# working.net
KiCad netlist of a schematic drawn in EAGLE
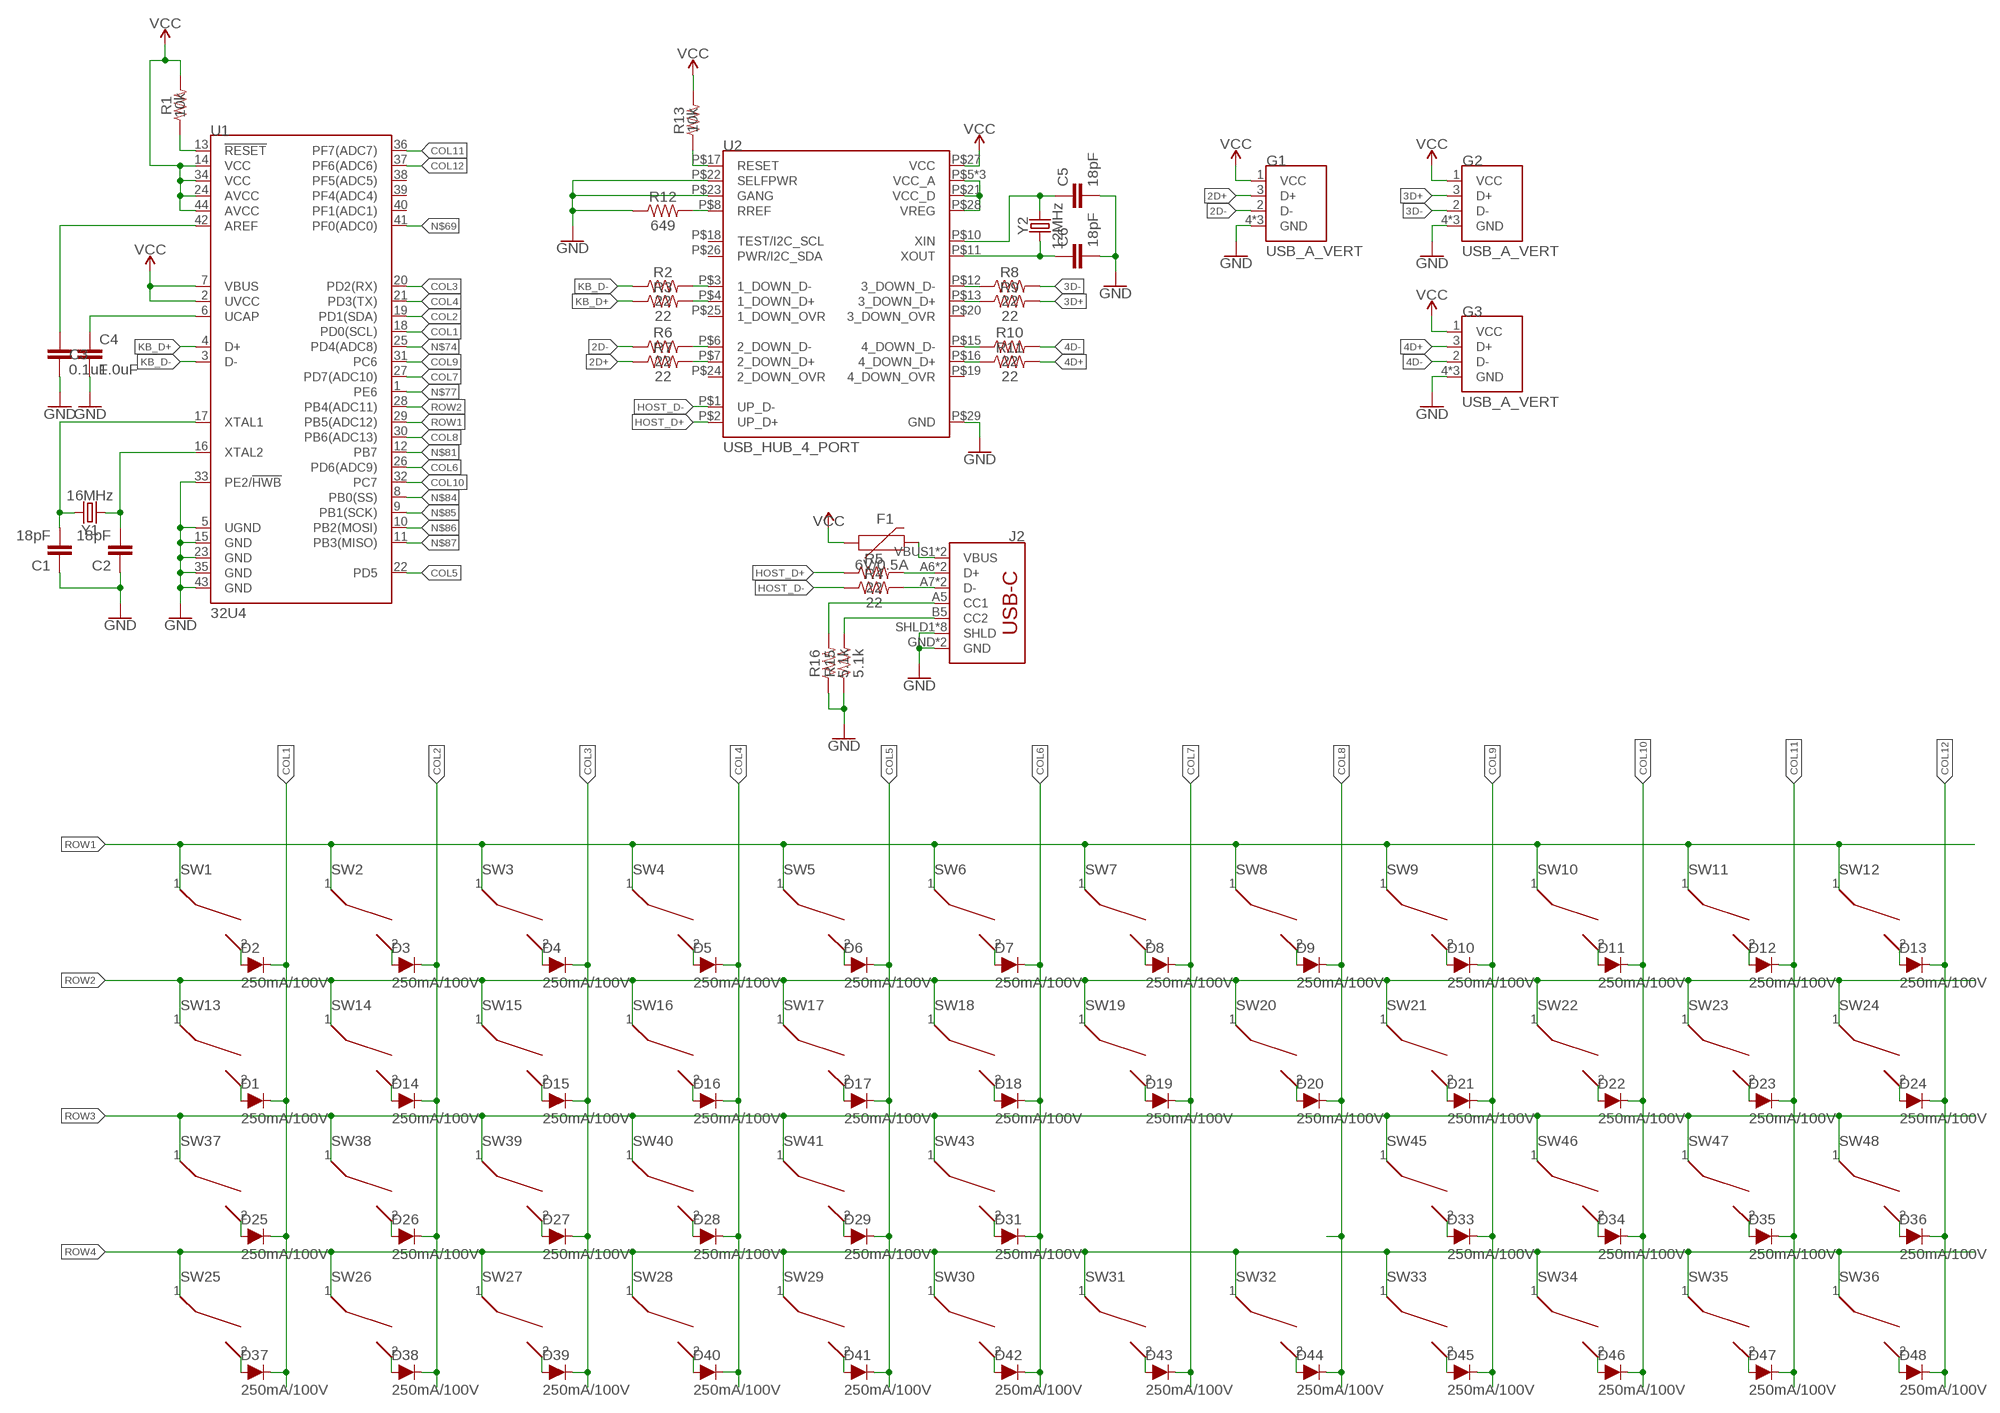
[diagram p0: schematic, sheet 1]

(export (version "E")
  (design (tool "Eeschema 10.0.6"))
  (components
    (comp (ref "C1")
      (value "18pF")
      (footprint "eagle-import:0603")
      (libsource (lib "eagle-import") (part "18PF-0603-50V-5%"))
    )
    (comp (ref "C2")
      (value "18pF")
      (footprint "eagle-import:0603")
      (libsource (lib "eagle-import") (part "18PF-0603-50V-5%"))
    )
    (comp (ref "C3")
      (value "0.1uF")
      (footprint "eagle-import:0603")
      (libsource (lib "eagle-import") (part "0.1UF-0603-25V-(+80/-20%)"))
    )
    (comp (ref "C4")
      (value "1.0uF")
      (footprint "eagle-import:0603")
      (libsource (lib "eagle-import") (part "1.0UF-0603-16V-10%"))
    )
    (comp (ref "C5")
      (value "18pF")
      (footprint "eagle-import:0603")
      (libsource (lib "eagle-import") (part "18PF-0603-50V-5%"))
    )
    (comp (ref "C6")
      (value "18pF")
      (footprint "eagle-import:0603")
      (libsource (lib "eagle-import") (part "18PF-0603-50V-5%"))
    )
    (comp (ref "D1")
      (value "250mA/100V")
      (footprint "eagle-import:SOD-323")
      (libsource (lib "eagle-import") (part "DIODE-BAS16J"))
    )
    (comp (ref "D2")
      (value "250mA/100V")
      (footprint "eagle-import:SOD-323")
      (libsource (lib "eagle-import") (part "DIODE-BAS16J"))
    )
    (comp (ref "D3")
      (value "250mA/100V")
      (footprint "eagle-import:SOD-323")
      (libsource (lib "eagle-import") (part "DIODE-BAS16J"))
    )
    (comp (ref "D4")
      (value "250mA/100V")
      (footprint "eagle-import:SOD-323")
      (libsource (lib "eagle-import") (part "DIODE-BAS16J"))
    )
    (comp (ref "D5")
      (value "250mA/100V")
      (footprint "eagle-import:SOD-323")
      (libsource (lib "eagle-import") (part "DIODE-BAS16J"))
    )
    (comp (ref "D6")
      (value "250mA/100V")
      (footprint "eagle-import:SOD-323")
      (libsource (lib "eagle-import") (part "DIODE-BAS16J"))
    )
    (comp (ref "D7")
      (value "250mA/100V")
      (footprint "eagle-import:SOD-323")
      (libsource (lib "eagle-import") (part "DIODE-BAS16J"))
    )
    (comp (ref "D8")
      (value "250mA/100V")
      (footprint "eagle-import:SOD-323")
      (libsource (lib "eagle-import") (part "DIODE-BAS16J"))
    )
    (comp (ref "D9")
      (value "250mA/100V")
      (footprint "eagle-import:SOD-323")
      (libsource (lib "eagle-import") (part "DIODE-BAS16J"))
    )
    (comp (ref "D10")
      (value "250mA/100V")
      (footprint "eagle-import:SOD-323")
      (libsource (lib "eagle-import") (part "DIODE-BAS16J"))
    )
    (comp (ref "D11")
      (value "250mA/100V")
      (footprint "eagle-import:SOD-323")
      (libsource (lib "eagle-import") (part "DIODE-BAS16J"))
    )
    (comp (ref "D12")
      (value "250mA/100V")
      (footprint "eagle-import:SOD-323")
      (libsource (lib "eagle-import") (part "DIODE-BAS16J"))
    )
    (comp (ref "D13")
      (value "250mA/100V")
      (footprint "eagle-import:SOD-323")
      (libsource (lib "eagle-import") (part "DIODE-BAS16J"))
    )
    (comp (ref "D14")
      (value "250mA/100V")
      (footprint "eagle-import:SOD-323")
      (libsource (lib "eagle-import") (part "DIODE-BAS16J"))
    )
    (comp (ref "D15")
      (value "250mA/100V")
      (footprint "eagle-import:SOD-323")
      (libsource (lib "eagle-import") (part "DIODE-BAS16J"))
    )
    (comp (ref "D16")
      (value "250mA/100V")
      (footprint "eagle-import:SOD-323")
      (libsource (lib "eagle-import") (part "DIODE-BAS16J"))
    )
    (comp (ref "D17")
      (value "250mA/100V")
      (footprint "eagle-import:SOD-323")
      (libsource (lib "eagle-import") (part "DIODE-BAS16J"))
    )
    (comp (ref "D18")
      (value "250mA/100V")
      (footprint "eagle-import:SOD-323")
      (libsource (lib "eagle-import") (part "DIODE-BAS16J"))
    )
    (comp (ref "D19")
      (value "250mA/100V")
      (footprint "eagle-import:SOD-323")
      (libsource (lib "eagle-import") (part "DIODE-BAS16J"))
    )
    (comp (ref "D20")
      (value "250mA/100V")
      (footprint "eagle-import:SOD-323")
      (libsource (lib "eagle-import") (part "DIODE-BAS16J"))
    )
    (comp (ref "D21")
      (value "250mA/100V")
      (footprint "eagle-import:SOD-323")
      (libsource (lib "eagle-import") (part "DIODE-BAS16J"))
    )
    (comp (ref "D22")
      (value "250mA/100V")
      (footprint "eagle-import:SOD-323")
      (libsource (lib "eagle-import") (part "DIODE-BAS16J"))
    )
    (comp (ref "D23")
      (value "250mA/100V")
      (footprint "eagle-import:SOD-323")
      (libsource (lib "eagle-import") (part "DIODE-BAS16J"))
    )
    (comp (ref "D24")
      (value "250mA/100V")
      (footprint "eagle-import:SOD-323")
      (libsource (lib "eagle-import") (part "DIODE-BAS16J"))
    )
    (comp (ref "D25")
      (value "250mA/100V")
      (footprint "eagle-import:SOD-323")
      (libsource (lib "eagle-import") (part "DIODE-BAS16J"))
    )
    (comp (ref "D26")
      (value "250mA/100V")
      (footprint "eagle-import:SOD-323")
      (libsource (lib "eagle-import") (part "DIODE-BAS16J"))
    )
    (comp (ref "D27")
      (value "250mA/100V")
      (footprint "eagle-import:SOD-323")
      (libsource (lib "eagle-import") (part "DIODE-BAS16J"))
    )
    (comp (ref "D28")
      (value "250mA/100V")
      (footprint "eagle-import:SOD-323")
      (libsource (lib "eagle-import") (part "DIODE-BAS16J"))
    )
    (comp (ref "D29")
      (value "250mA/100V")
      (footprint "eagle-import:SOD-323")
      (libsource (lib "eagle-import") (part "DIODE-BAS16J"))
    )
    (comp (ref "D31")
      (value "250mA/100V")
      (footprint "eagle-import:SOD-323")
      (libsource (lib "eagle-import") (part "DIODE-BAS16J"))
    )
    (comp (ref "D33")
      (value "250mA/100V")
      (footprint "eagle-import:SOD-323")
      (libsource (lib "eagle-import") (part "DIODE-BAS16J"))
    )
    (comp (ref "D34")
      (value "250mA/100V")
      (footprint "eagle-import:SOD-323")
      (libsource (lib "eagle-import") (part "DIODE-BAS16J"))
    )
    (comp (ref "D35")
      (value "250mA/100V")
      (footprint "eagle-import:SOD-323")
      (libsource (lib "eagle-import") (part "DIODE-BAS16J"))
    )
    (comp (ref "D36")
      (value "250mA/100V")
      (footprint "eagle-import:SOD-323")
      (libsource (lib "eagle-import") (part "DIODE-BAS16J"))
    )
    (comp (ref "D37")
      (value "250mA/100V")
      (footprint "eagle-import:SOD-323")
      (libsource (lib "eagle-import") (part "DIODE-BAS16J"))
    )
    (comp (ref "D38")
      (value "250mA/100V")
      (footprint "eagle-import:SOD-323")
      (libsource (lib "eagle-import") (part "DIODE-BAS16J"))
    )
    (comp (ref "D39")
      (value "250mA/100V")
      (footprint "eagle-import:SOD-323")
      (libsource (lib "eagle-import") (part "DIODE-BAS16J"))
    )
    (comp (ref "D40")
      (value "250mA/100V")
      (footprint "eagle-import:SOD-323")
      (libsource (lib "eagle-import") (part "DIODE-BAS16J"))
    )
    (comp (ref "D41")
      (value "250mA/100V")
      (footprint "eagle-import:SOD-323")
      (libsource (lib "eagle-import") (part "DIODE-BAS16J"))
    )
    (comp (ref "D42")
      (value "250mA/100V")
      (footprint "eagle-import:SOD-323")
      (libsource (lib "eagle-import") (part "DIODE-BAS16J"))
    )
    (comp (ref "D43")
      (value "250mA/100V")
      (footprint "eagle-import:SOD-323")
      (libsource (lib "eagle-import") (part "DIODE-BAS16J"))
    )
    (comp (ref "D44")
      (value "250mA/100V")
      (footprint "eagle-import:SOD-323")
      (libsource (lib "eagle-import") (part "DIODE-BAS16J"))
    )
    (comp (ref "D45")
      (value "250mA/100V")
      (footprint "eagle-import:SOD-323")
      (libsource (lib "eagle-import") (part "DIODE-BAS16J"))
    )
    (comp (ref "D46")
      (value "250mA/100V")
      (footprint "eagle-import:SOD-323")
      (libsource (lib "eagle-import") (part "DIODE-BAS16J"))
    )
    (comp (ref "D47")
      (value "250mA/100V")
      (footprint "eagle-import:SOD-323")
      (libsource (lib "eagle-import") (part "DIODE-BAS16J"))
    )
    (comp (ref "D48")
      (value "250mA/100V")
      (footprint "eagle-import:SOD-323")
      (libsource (lib "eagle-import") (part "DIODE-BAS16J"))
    )
    (comp (ref "F1")
      (value "6V/0.5A")
      (footprint "eagle-import:1206")
      (libsource (lib "eagle-import") (part "PPTC_6V500MA-2"))
    )
    (comp (ref "G1")
      (value "USB_A_VERT")
      (footprint "eagle-import:USB_A_VERT")
      (libsource (lib "eagle-import") (part "USB_A_VERT"))
    )
    (comp (ref "G2")
      (value "USB_A_VERT")
      (footprint "eagle-import:USB_A_VERT")
      (libsource (lib "eagle-import") (part "USB_A_VERT"))
    )
    (comp (ref "G3")
      (value "USB_A_VERT")
      (footprint "eagle-import:USB_A_VERT")
      (libsource (lib "eagle-import") (part "USB_A_VERT"))
    )
    (comp (ref "J2")
      (value "USB_C2-LAYER")
      (footprint "eagle-import:USB-C-16P")
      (libsource (lib "eagle-import") (part "USB_C2-LAYER"))
    )
    (comp (ref "R1")
      (value "10k")
      (footprint "eagle-import:0603")
      (libsource (lib "eagle-import") (part "10KOHM-0603-1/10W-1%"))
    )
    (comp (ref "R2")
      (value "22")
      (footprint "eagle-import:0603")
      (libsource (lib "eagle-import") (part "22OHM-0603-1/10W-1%"))
    )
    (comp (ref "R3")
      (value "22")
      (footprint "eagle-import:0603")
      (libsource (lib "eagle-import") (part "22OHM-0603-1/10W-1%"))
    )
    (comp (ref "R4")
      (value "22")
      (footprint "eagle-import:0603")
      (libsource (lib "eagle-import") (part "22OHM-0603-1/10W-1%"))
    )
    (comp (ref "R5")
      (value "22")
      (footprint "eagle-import:0603")
      (libsource (lib "eagle-import") (part "22OHM-0603-1/10W-1%"))
    )
    (comp (ref "R6")
      (value "22")
      (footprint "eagle-import:0603")
      (libsource (lib "eagle-import") (part "22OHM-0603-1/10W-1%"))
    )
    (comp (ref "R7")
      (value "22")
      (footprint "eagle-import:0603")
      (libsource (lib "eagle-import") (part "22OHM-0603-1/10W-1%"))
    )
    (comp (ref "R8")
      (value "22")
      (footprint "eagle-import:0603")
      (libsource (lib "eagle-import") (part "22OHM-0603-1/10W-1%"))
    )
    (comp (ref "R9")
      (value "22")
      (footprint "eagle-import:0603")
      (libsource (lib "eagle-import") (part "22OHM-0603-1/10W-1%"))
    )
    (comp (ref "R10")
      (value "22")
      (footprint "eagle-import:0603")
      (libsource (lib "eagle-import") (part "22OHM-0603-1/10W-1%"))
    )
    (comp (ref "R11")
      (value "22")
      (footprint "eagle-import:0603")
      (libsource (lib "eagle-import") (part "22OHM-0603-1/10W-1%"))
    )
    (comp (ref "R12")
      (value "649")
      (footprint "eagle-import:0603")
      (libsource (lib "eagle-import") (part "680OHM-0603-1/10W-5%"))
    )
    (comp (ref "R13")
      (value "10k")
      (footprint "eagle-import:0603")
      (libsource (lib "eagle-import") (part "10KOHM-0603-1/10W-1%"))
    )
    (comp (ref "R15")
      (value "5.1k")
      (footprint "eagle-import:0603")
      (libsource (lib "eagle-import") (part "5.1KOHM5.1KOHM-0603-1/10W-1%"))
    )
    (comp (ref "R16")
      (value "5.1k")
      (footprint "eagle-import:0603")
      (libsource (lib "eagle-import") (part "5.1KOHM5.1KOHM-0603-1/10W-1%"))
    )
    (comp (ref "SW1")
      (value "CHERRY_MX_WITH_FIXING_PINS")
      (footprint "eagle-import:MX1A-XXNW")
      (libsource (lib "eagle-import") (part "CHERRY_MX_WITH_FIXING_PINS"))
    )
    (comp (ref "SW2")
      (value "CHERRY_MX_WITH_FIXING_PINS")
      (footprint "eagle-import:MX1A-XXNW")
      (libsource (lib "eagle-import") (part "CHERRY_MX_WITH_FIXING_PINS"))
    )
    (comp (ref "SW3")
      (value "CHERRY_MX_WITH_FIXING_PINS")
      (footprint "eagle-import:MX1A-XXNW")
      (libsource (lib "eagle-import") (part "CHERRY_MX_WITH_FIXING_PINS"))
    )
    (comp (ref "SW4")
      (value "CHERRY_MX_WITH_FIXING_PINS")
      (footprint "eagle-import:MX1A-XXNW")
      (libsource (lib "eagle-import") (part "CHERRY_MX_WITH_FIXING_PINS"))
    )
    (comp (ref "SW5")
      (value "CHERRY_MX_WITH_FIXING_PINS")
      (footprint "eagle-import:MX1A-XXNW")
      (libsource (lib "eagle-import") (part "CHERRY_MX_WITH_FIXING_PINS"))
    )
    (comp (ref "SW6")
      (value "CHERRY_MX_WITH_FIXING_PINS")
      (footprint "eagle-import:MX1A-XXNW")
      (libsource (lib "eagle-import") (part "CHERRY_MX_WITH_FIXING_PINS"))
    )
    (comp (ref "SW7")
      (value "CHERRY_MX_WITH_FIXING_PINS")
      (footprint "eagle-import:MX1A-XXNW")
      (libsource (lib "eagle-import") (part "CHERRY_MX_WITH_FIXING_PINS"))
    )
    (comp (ref "SW8")
      (value "CHERRY_MX_WITH_FIXING_PINS")
      (footprint "eagle-import:MX1A-XXNW")
      (libsource (lib "eagle-import") (part "CHERRY_MX_WITH_FIXING_PINS"))
    )
    (comp (ref "SW9")
      (value "CHERRY_MX_WITH_FIXING_PINS")
      (footprint "eagle-import:MX1A-XXNW")
      (libsource (lib "eagle-import") (part "CHERRY_MX_WITH_FIXING_PINS"))
    )
    (comp (ref "SW10")
      (value "CHERRY_MX_WITH_FIXING_PINS")
      (footprint "eagle-import:MX1A-XXNW")
      (libsource (lib "eagle-import") (part "CHERRY_MX_WITH_FIXING_PINS"))
    )
    (comp (ref "SW11")
      (value "CHERRY_MX_WITH_FIXING_PINS")
      (footprint "eagle-import:MX1A-XXNW")
      (libsource (lib "eagle-import") (part "CHERRY_MX_WITH_FIXING_PINS"))
    )
    (comp (ref "SW12")
      (value "CHERRY_MX_WITH_FIXING_PINS")
      (footprint "eagle-import:MX1A-XXNW")
      (libsource (lib "eagle-import") (part "CHERRY_MX_WITH_FIXING_PINS"))
    )
    (comp (ref "SW13")
      (value "CHERRY_MX_WITH_FIXING_PINS")
      (footprint "eagle-import:MX1A-XXNW")
      (libsource (lib "eagle-import") (part "CHERRY_MX_WITH_FIXING_PINS"))
    )
    (comp (ref "SW14")
      (value "CHERRY_MX_WITH_FIXING_PINS")
      (footprint "eagle-import:MX1A-XXNW")
      (libsource (lib "eagle-import") (part "CHERRY_MX_WITH_FIXING_PINS"))
    )
    (comp (ref "SW15")
      (value "CHERRY_MX_WITH_FIXING_PINS")
      (footprint "eagle-import:MX1A-XXNW")
      (libsource (lib "eagle-import") (part "CHERRY_MX_WITH_FIXING_PINS"))
    )
    (comp (ref "SW16")
      (value "CHERRY_MX_WITH_FIXING_PINS")
      (footprint "eagle-import:MX1A-XXNW")
      (libsource (lib "eagle-import") (part "CHERRY_MX_WITH_FIXING_PINS"))
    )
    (comp (ref "SW17")
      (value "CHERRY_MX_WITH_FIXING_PINS")
      (footprint "eagle-import:MX1A-XXNW")
      (libsource (lib "eagle-import") (part "CHERRY_MX_WITH_FIXING_PINS"))
    )
    (comp (ref "SW18")
      (value "CHERRY_MX_WITH_FIXING_PINS")
      (footprint "eagle-import:MX1A-XXNW")
      (libsource (lib "eagle-import") (part "CHERRY_MX_WITH_FIXING_PINS"))
    )
    (comp (ref "SW19")
      (value "CHERRY_MX_WITH_FIXING_PINS")
      (footprint "eagle-import:MX1A-XXNW")
      (libsource (lib "eagle-import") (part "CHERRY_MX_WITH_FIXING_PINS"))
    )
    (comp (ref "SW20")
      (value "CHERRY_MX_WITH_FIXING_PINS")
      (footprint "eagle-import:MX1A-XXNW")
      (libsource (lib "eagle-import") (part "CHERRY_MX_WITH_FIXING_PINS"))
    )
    (comp (ref "SW21")
      (value "CHERRY_MX_WITH_FIXING_PINS")
      (footprint "eagle-import:MX1A-XXNW")
      (libsource (lib "eagle-import") (part "CHERRY_MX_WITH_FIXING_PINS"))
    )
    (comp (ref "SW22")
      (value "CHERRY_MX_WITH_FIXING_PINS")
      (footprint "eagle-import:MX1A-XXNW")
      (libsource (lib "eagle-import") (part "CHERRY_MX_WITH_FIXING_PINS"))
    )
    (comp (ref "SW23")
      (value "CHERRY_MX_WITH_FIXING_PINS")
      (footprint "eagle-import:MX1A-XXNW")
      (libsource (lib "eagle-import") (part "CHERRY_MX_WITH_FIXING_PINS"))
    )
    (comp (ref "SW24")
      (value "CHERRY_MX_WITH_FIXING_PINS")
      (footprint "eagle-import:MX1A-XXNW")
      (libsource (lib "eagle-import") (part "CHERRY_MX_WITH_FIXING_PINS"))
    )
    (comp (ref "SW25")
      (value "CHERRY_MX_WITH_FIXING_PINS")
      (footprint "eagle-import:MX1A-XXNW")
      (libsource (lib "eagle-import") (part "CHERRY_MX_WITH_FIXING_PINS"))
    )
    (comp (ref "SW26")
      (value "CHERRY_MX_WITH_FIXING_PINS")
      (footprint "eagle-import:MX1A-XXNW")
      (libsource (lib "eagle-import") (part "CHERRY_MX_WITH_FIXING_PINS"))
    )
    (comp (ref "SW27")
      (value "CHERRY_MX_WITH_FIXING_PINS")
      (footprint "eagle-import:MX1A-XXNW")
      (libsource (lib "eagle-import") (part "CHERRY_MX_WITH_FIXING_PINS"))
    )
    (comp (ref "SW28")
      (value "CHERRY_MX_WITH_FIXING_PINS")
      (footprint "eagle-import:MX1A-XXNW")
      (libsource (lib "eagle-import") (part "CHERRY_MX_WITH_FIXING_PINS"))
    )
    (comp (ref "SW29")
      (value "CHERRY_MX_WITH_FIXING_PINS")
      (footprint "eagle-import:MX1A-XXNW")
      (libsource (lib "eagle-import") (part "CHERRY_MX_WITH_FIXING_PINS"))
    )
    (comp (ref "SW30")
      (value "CHERRY_MX_WITH_FIXING_PINS")
      (footprint "eagle-import:MX1A-XXNW")
      (libsource (lib "eagle-import") (part "CHERRY_MX_WITH_FIXING_PINS"))
    )
    (comp (ref "SW31")
      (value "CHERRY_MX_WITH_FIXING_PINS")
      (footprint "eagle-import:MX1A-XXNW")
      (libsource (lib "eagle-import") (part "CHERRY_MX_WITH_FIXING_PINS"))
    )
    (comp (ref "SW32")
      (value "CHERRY_MX_WITH_FIXING_PINS")
      (footprint "eagle-import:MX1A-XXNW")
      (libsource (lib "eagle-import") (part "CHERRY_MX_WITH_FIXING_PINS"))
    )
    (comp (ref "SW33")
      (value "CHERRY_MX_WITH_FIXING_PINS")
      (footprint "eagle-import:MX1A-XXNW")
      (libsource (lib "eagle-import") (part "CHERRY_MX_WITH_FIXING_PINS"))
    )
    (comp (ref "SW34")
      (value "CHERRY_MX_WITH_FIXING_PINS")
      (footprint "eagle-import:MX1A-XXNW")
      (libsource (lib "eagle-import") (part "CHERRY_MX_WITH_FIXING_PINS"))
    )
    (comp (ref "SW35")
      (value "CHERRY_MX_WITH_FIXING_PINS")
      (footprint "eagle-import:MX1A-XXNW")
      (libsource (lib "eagle-import") (part "CHERRY_MX_WITH_FIXING_PINS"))
    )
    (comp (ref "SW36")
      (value "CHERRY_MX_WITH_FIXING_PINS")
      (footprint "eagle-import:MX1A-XXNW")
      (libsource (lib "eagle-import") (part "CHERRY_MX_WITH_FIXING_PINS"))
    )
    (comp (ref "SW37")
      (value "CHERRY_MX_WITH_FIXING_PINS")
      (footprint "eagle-import:MX1A-XXNW")
      (libsource (lib "eagle-import") (part "CHERRY_MX_WITH_FIXING_PINS"))
    )
    (comp (ref "SW38")
      (value "CHERRY_MX_WITH_FIXING_PINS")
      (footprint "eagle-import:MX1A-XXNW")
      (libsource (lib "eagle-import") (part "CHERRY_MX_WITH_FIXING_PINS"))
    )
    (comp (ref "SW39")
      (value "CHERRY_MX_WITH_FIXING_PINS")
      (footprint "eagle-import:MX1A-XXNW")
      (libsource (lib "eagle-import") (part "CHERRY_MX_WITH_FIXING_PINS"))
    )
    (comp (ref "SW40")
      (value "CHERRY_MX_WITH_FIXING_PINS")
      (footprint "eagle-import:MX1A-XXNW")
      (libsource (lib "eagle-import") (part "CHERRY_MX_WITH_FIXING_PINS"))
    )
    (comp (ref "SW41")
      (value "CHERRY_MX_WITH_FIXING_PINS")
      (footprint "eagle-import:MX1A-XXNW")
      (libsource (lib "eagle-import") (part "CHERRY_MX_WITH_FIXING_PINS"))
    )
    (comp (ref "SW43")
      (value "CHERRY_MX_WITH_FIXING_PINS")
      (footprint "eagle-import:MX1A-XXNW")
      (libsource (lib "eagle-import") (part "CHERRY_MX_WITH_FIXING_PINS"))
    )
    (comp (ref "SW45")
      (value "CHERRY_MX_WITH_FIXING_PINS")
      (footprint "eagle-import:MX1A-XXNW")
      (libsource (lib "eagle-import") (part "CHERRY_MX_WITH_FIXING_PINS"))
    )
    (comp (ref "SW46")
      (value "CHERRY_MX_WITH_FIXING_PINS")
      (footprint "eagle-import:MX1A-XXNW")
      (libsource (lib "eagle-import") (part "CHERRY_MX_WITH_FIXING_PINS"))
    )
    (comp (ref "SW47")
      (value "CHERRY_MX_WITH_FIXING_PINS")
      (footprint "eagle-import:MX1A-XXNW")
      (libsource (lib "eagle-import") (part "CHERRY_MX_WITH_FIXING_PINS"))
    )
    (comp (ref "SW48")
      (value "CHERRY_MX_WITH_FIXING_PINS")
      (footprint "eagle-import:MX1A-XXNW")
      (libsource (lib "eagle-import") (part "CHERRY_MX_WITH_FIXING_PINS"))
    )
    (comp (ref "U1")
      (value "32U4")
      (footprint "eagle-import:QFN-44-NOPAD_1_1")
      (libsource (lib "eagle-import") (part "ATMEGA32U41{colon}1"))
    )
    (comp (ref "U2")
      (value "USB_HUB_4_PORT")
      (footprint "eagle-import:QFN-28-5MM-1_1")
      (libsource (lib "eagle-import") (part "USB_HUB_4_PORT"))
    )
    (comp (ref "Y1")
      (value "16MHz")
      (footprint "eagle-import:CRYSTAL-SMD-5X3.2-4PAD")
      (libsource (lib "eagle-import") (part "CRYSTAL-16MHZSMD-5X3.2"))
    )
    (comp (ref "Y2")
      (value "12MHz")
      (footprint "eagle-import:CRYSTAL-SMD-5X3.2-4PAD")
      (libsource (lib "eagle-import") (part "CRYSTAL-12MHZ{dblquote}"))
    )
  )
  (nets
    (net (code "1") (name "2D+") (class "Default")
      (node (ref "G1") (pin "3") (pinfunction "D+_3") (pintype "bidirectional"))
      (node (ref "R7") (pin "1") (pinfunction "1_1") (pintype "passive"))
    )
    (net (code "2") (name "2D-") (class "Default")
      (node (ref "G1") (pin "2") (pinfunction "D-_2") (pintype "bidirectional"))
      (node (ref "R6") (pin "1") (pinfunction "1_1") (pintype "passive"))
    )
    (net (code "3") (name "3D+") (class "Default")
      (node (ref "G2") (pin "3") (pinfunction "D+_3") (pintype "bidirectional"))
      (node (ref "R9") (pin "2") (pinfunction "2_2") (pintype "passive"))
    )
    (net (code "4") (name "3D-") (class "Default")
      (node (ref "G2") (pin "2") (pinfunction "D-_2") (pintype "bidirectional"))
      (node (ref "R8") (pin "2") (pinfunction "2_2") (pintype "passive"))
    )
    (net (code "5") (name "4D+") (class "Default")
      (node (ref "G3") (pin "3") (pinfunction "D+_3") (pintype "bidirectional"))
      (node (ref "R11") (pin "2") (pinfunction "2_2") (pintype "passive"))
    )
    (net (code "6") (name "4D-") (class "Default")
      (node (ref "G3") (pin "2") (pinfunction "D-_2") (pintype "bidirectional"))
      (node (ref "R10") (pin "2") (pinfunction "2_2") (pintype "passive"))
    )
    (net (code "7") (name "COL1") (class "Default")
      (node (ref "D1") (pin "C") (pinfunction "C_C") (pintype "passive"))
      (node (ref "D2") (pin "C") (pinfunction "C_C") (pintype "passive"))
      (node (ref "D25") (pin "C") (pinfunction "C_C") (pintype "passive"))
      (node (ref "D37") (pin "C") (pinfunction "C_C") (pintype "passive"))
      (node (ref "U1") (pin "18") (pinfunction "PD0(SCL)_18") (pintype "bidirectional"))
    )
    (net (code "8") (name "COL2") (class "Default")
      (node (ref "D14") (pin "C") (pinfunction "C_C") (pintype "passive"))
      (node (ref "D26") (pin "C") (pinfunction "C_C") (pintype "passive"))
      (node (ref "D3") (pin "C") (pinfunction "C_C") (pintype "passive"))
      (node (ref "D38") (pin "C") (pinfunction "C_C") (pintype "passive"))
      (node (ref "U1") (pin "19") (pinfunction "PD1(SDA)_19") (pintype "bidirectional"))
    )
    (net (code "9") (name "COL3") (class "Default")
      (node (ref "D15") (pin "C") (pinfunction "C_C") (pintype "passive"))
      (node (ref "D27") (pin "C") (pinfunction "C_C") (pintype "passive"))
      (node (ref "D39") (pin "C") (pinfunction "C_C") (pintype "passive"))
      (node (ref "D4") (pin "C") (pinfunction "C_C") (pintype "passive"))
      (node (ref "U1") (pin "20") (pinfunction "PD2(RX)_20") (pintype "bidirectional"))
    )
    (net (code "10") (name "COL4") (class "Default")
      (node (ref "D16") (pin "C") (pinfunction "C_C") (pintype "passive"))
      (node (ref "D28") (pin "C") (pinfunction "C_C") (pintype "passive"))
      (node (ref "D40") (pin "C") (pinfunction "C_C") (pintype "passive"))
      (node (ref "D5") (pin "C") (pinfunction "C_C") (pintype "passive"))
      (node (ref "U1") (pin "21") (pinfunction "PD3(TX)_21") (pintype "bidirectional"))
    )
    (net (code "11") (name "COL5") (class "Default")
      (node (ref "D17") (pin "C") (pinfunction "C_C") (pintype "passive"))
      (node (ref "D29") (pin "C") (pinfunction "C_C") (pintype "passive"))
      (node (ref "D41") (pin "C") (pinfunction "C_C") (pintype "passive"))
      (node (ref "D6") (pin "C") (pinfunction "C_C") (pintype "passive"))
      (node (ref "U1") (pin "22") (pinfunction "PD5_22") (pintype "bidirectional"))
    )
    (net (code "12") (name "COL6") (class "Default")
      (node (ref "D18") (pin "C") (pinfunction "C_C") (pintype "passive"))
      (node (ref "D31") (pin "C") (pinfunction "C_C") (pintype "passive"))
      (node (ref "D42") (pin "C") (pinfunction "C_C") (pintype "passive"))
      (node (ref "D7") (pin "C") (pinfunction "C_C") (pintype "passive"))
      (node (ref "U1") (pin "26") (pinfunction "PD6(ADC9)_26") (pintype "bidirectional"))
    )
    (net (code "13") (name "COL7") (class "Default")
      (node (ref "D19") (pin "C") (pinfunction "C_C") (pintype "passive"))
      (node (ref "D43") (pin "C") (pinfunction "C_C") (pintype "passive"))
      (node (ref "D8") (pin "C") (pinfunction "C_C") (pintype "passive"))
      (node (ref "U1") (pin "27") (pinfunction "PD7(ADC10)_27") (pintype "bidirectional"))
    )
    (net (code "14") (name "COL8") (class "Default")
      (node (ref "D20") (pin "C") (pinfunction "C_C") (pintype "passive"))
      (node (ref "D44") (pin "C") (pinfunction "C_C") (pintype "passive"))
      (node (ref "D9") (pin "C") (pinfunction "C_C") (pintype "passive"))
      (node (ref "U1") (pin "30") (pinfunction "PB6(ADC13)_30") (pintype "bidirectional"))
    )
    (net (code "15") (name "COL9") (class "Default")
      (node (ref "D10") (pin "C") (pinfunction "C_C") (pintype "passive"))
      (node (ref "D21") (pin "C") (pinfunction "C_C") (pintype "passive"))
      (node (ref "D33") (pin "C") (pinfunction "C_C") (pintype "passive"))
      (node (ref "D45") (pin "C") (pinfunction "C_C") (pintype "passive"))
      (node (ref "U1") (pin "31") (pinfunction "PC6_31") (pintype "bidirectional"))
    )
    (net (code "16") (name "COL10") (class "Default")
      (node (ref "D11") (pin "C") (pinfunction "C_C") (pintype "passive"))
      (node (ref "D22") (pin "C") (pinfunction "C_C") (pintype "passive"))
      (node (ref "D34") (pin "C") (pinfunction "C_C") (pintype "passive"))
      (node (ref "D46") (pin "C") (pinfunction "C_C") (pintype "passive"))
      (node (ref "U1") (pin "32") (pinfunction "PC7_32") (pintype "bidirectional"))
    )
    (net (code "17") (name "COL11") (class "Default")
      (node (ref "D12") (pin "C") (pinfunction "C_C") (pintype "passive"))
      (node (ref "D23") (pin "C") (pinfunction "C_C") (pintype "passive"))
      (node (ref "D35") (pin "C") (pinfunction "C_C") (pintype "passive"))
      (node (ref "D47") (pin "C") (pinfunction "C_C") (pintype "passive"))
      (node (ref "U1") (pin "36") (pinfunction "PF7(ADC7)_36") (pintype "bidirectional"))
    )
    (net (code "18") (name "COL12") (class "Default")
      (node (ref "D13") (pin "C") (pinfunction "C_C") (pintype "passive"))
      (node (ref "D24") (pin "C") (pinfunction "C_C") (pintype "passive"))
      (node (ref "D36") (pin "C") (pinfunction "C_C") (pintype "passive"))
      (node (ref "D48") (pin "C") (pinfunction "C_C") (pintype "passive"))
      (node (ref "U1") (pin "37") (pinfunction "PF6(ADC6)_37") (pintype "bidirectional"))
    )
    (net (code "19") (name "GND") (class "Default")
      (node (ref "C1") (pin "1") (pinfunction "1_1") (pintype "passive"))
      (node (ref "C2") (pin "1") (pinfunction "1_1") (pintype "passive"))
      (node (ref "C3") (pin "2") (pinfunction "2_2") (pintype "passive"))
      (node (ref "C4") (pin "2") (pinfunction "2_2") (pintype "passive"))
      (node (ref "C5") (pin "2") (pinfunction "2_2") (pintype "passive"))
      (node (ref "C6") (pin "2") (pinfunction "2_2") (pintype "passive"))
      (node (ref "G1") (pin "4") (pinfunction "GND_4") (pintype "bidirectional"))
      (node (ref "G1") (pin "SHIELD_1") (pinfunction "GND_SHIELD_1") (pintype "bidirectional"))
      (node (ref "G1") (pin "SHIELD_2") (pinfunction "GND_SHIELD_2") (pintype "bidirectional"))
      (node (ref "G2") (pin "4") (pinfunction "GND_4") (pintype "bidirectional"))
      (node (ref "G2") (pin "SHIELD_1") (pinfunction "GND_SHIELD_1") (pintype "bidirectional"))
      (node (ref "G2") (pin "SHIELD_2") (pinfunction "GND_SHIELD_2") (pintype "bidirectional"))
      (node (ref "G3") (pin "4") (pinfunction "GND_4") (pintype "bidirectional"))
      (node (ref "G3") (pin "SHIELD_1") (pinfunction "GND_SHIELD_1") (pintype "bidirectional"))
      (node (ref "G3") (pin "SHIELD_2") (pinfunction "GND_SHIELD_2") (pintype "bidirectional"))
      (node (ref "J2") (pin "GND") (pinfunction "GND_GND") (pintype "bidirectional"))
      (node (ref "J2") (pin "GND2") (pinfunction "GND_GND2") (pintype "bidirectional"))
      (node (ref "J2") (pin "SHLD1") (pinfunction "SHLD_SHLD1") (pintype "bidirectional"))
      (node (ref "J2") (pin "SHLD2") (pinfunction "SHLD_SHLD2") (pintype "bidirectional"))
      (node (ref "J2") (pin "SHLD3") (pinfunction "SHLD_SHLD3") (pintype "bidirectional"))
      (node (ref "J2") (pin "SHLD4") (pinfunction "SHLD_SHLD4") (pintype "bidirectional"))
      (node (ref "J2") (pin "SHLD5") (pinfunction "SHLD_SHLD5") (pintype "bidirectional"))
      (node (ref "J2") (pin "SHLD6") (pinfunction "SHLD_SHLD6") (pintype "bidirectional"))
      (node (ref "J2") (pin "SHLD7") (pinfunction "SHLD_SHLD7") (pintype "bidirectional"))
      (node (ref "J2") (pin "SHLD8") (pinfunction "SHLD_SHLD8") (pintype "bidirectional"))
      (node (ref "R12") (pin "1") (pinfunction "1_1") (pintype "passive"))
      (node (ref "R15") (pin "1") (pinfunction "1_1") (pintype "passive"))
      (node (ref "R16") (pin "1") (pinfunction "1_1") (pintype "passive"))
      (node (ref "U1") (pin "15") (pinfunction "GND_15") (pintype "bidirectional"))
      (node (ref "U1") (pin "23") (pinfunction "GND_23") (pintype "bidirectional"))
      (node (ref "U1") (pin "33") (pinfunction "PE2/~{HWB}_33") (pintype "bidirectional"))
      (node (ref "U1") (pin "35") (pinfunction "GND_35") (pintype "bidirectional"))
      (node (ref "U1") (pin "43") (pinfunction "GND_43") (pintype "bidirectional"))
      (node (ref "U1") (pin "5") (pinfunction "UGND_5") (pintype "bidirectional"))
      (node (ref "U2") (pin "P$22") (pinfunction "SELFPWR_P$22") (pintype "bidirectional"))
      (node (ref "U2") (pin "P$23") (pinfunction "GANG_P$23") (pintype "bidirectional"))
      (node (ref "U2") (pin "P$29") (pinfunction "GND_P$29") (pintype "bidirectional"))
    )
    (net (code "20") (name "HOST_D+") (class "Default")
      (node (ref "R5") (pin "1") (pinfunction "1_1") (pintype "passive"))
      (node (ref "U2") (pin "P$2") (pinfunction "UP_D+_P$2") (pintype "bidirectional"))
    )
    (net (code "21") (name "HOST_D-") (class "Default")
      (node (ref "R4") (pin "1") (pinfunction "1_1") (pintype "passive"))
      (node (ref "U2") (pin "P$1") (pinfunction "UP_D-_P$1") (pintype "bidirectional"))
    )
    (net (code "22") (name "KB_D+") (class "Default")
      (node (ref "R3") (pin "1") (pinfunction "1_1") (pintype "passive"))
      (node (ref "U1") (pin "4") (pinfunction "D+_4") (pintype "bidirectional"))
    )
    (net (code "23") (name "KB_D-") (class "Default")
      (node (ref "R2") (pin "1") (pinfunction "1_1") (pintype "passive"))
      (node (ref "U1") (pin "3") (pinfunction "D-_3") (pintype "bidirectional"))
    )
    (net (code "24") (name "N$69") (class "Default")
      (node (ref "U1") (pin "41") (pinfunction "PF0(ADC0)_41") (pintype "bidirectional"))
    )
    (net (code "25") (name "N$74") (class "Default")
      (node (ref "U1") (pin "25") (pinfunction "PD4(ADC8)_25") (pintype "bidirectional"))
    )
    (net (code "26") (name "N$77") (class "Default")
      (node (ref "U1") (pin "1") (pinfunction "PE6_1") (pintype "bidirectional"))
    )
    (net (code "27") (name "N$81") (class "Default")
      (node (ref "U1") (pin "12") (pinfunction "PB7_12") (pintype "bidirectional"))
    )
    (net (code "28") (name "N$84") (class "Default")
      (node (ref "U1") (pin "8") (pinfunction "PB0(SS)_8") (pintype "bidirectional"))
    )
    (net (code "29") (name "N$85") (class "Default")
      (node (ref "U1") (pin "9") (pinfunction "PB1(SCK)_9") (pintype "bidirectional"))
    )
    (net (code "30") (name "N$86") (class "Default")
      (node (ref "U1") (pin "10") (pinfunction "PB2(MOSI)_10") (pintype "bidirectional"))
    )
    (net (code "31") (name "N$87") (class "Default")
      (node (ref "U1") (pin "11") (pinfunction "PB3(MISO)_11") (pintype "bidirectional"))
    )
    (net (code "32") (name "Net-(D1-PadA)") (class "Default")
      (node (ref "D1") (pin "A") (pinfunction "A_A") (pintype "passive"))
      (node (ref "SW13") (pin "2") (pinfunction "2_2") (pintype "passive"))
    )
    (net (code "33") (name "Net-(D2-PadA)") (class "Default")
      (node (ref "D2") (pin "A") (pinfunction "A_A") (pintype "passive"))
      (node (ref "SW1") (pin "2") (pinfunction "2_2") (pintype "passive"))
    )
    (net (code "34") (name "Net-(D3-PadA)") (class "Default")
      (node (ref "D3") (pin "A") (pinfunction "A_A") (pintype "passive"))
      (node (ref "SW2") (pin "2") (pinfunction "2_2") (pintype "passive"))
    )
    (net (code "35") (name "Net-(D4-PadA)") (class "Default")
      (node (ref "D4") (pin "A") (pinfunction "A_A") (pintype "passive"))
      (node (ref "SW3") (pin "2") (pinfunction "2_2") (pintype "passive"))
    )
    (net (code "36") (name "Net-(D5-PadA)") (class "Default")
      (node (ref "D5") (pin "A") (pinfunction "A_A") (pintype "passive"))
      (node (ref "SW4") (pin "2") (pinfunction "2_2") (pintype "passive"))
    )
    (net (code "37") (name "Net-(D6-PadA)") (class "Default")
      (node (ref "D6") (pin "A") (pinfunction "A_A") (pintype "passive"))
      (node (ref "SW5") (pin "2") (pinfunction "2_2") (pintype "passive"))
    )
    (net (code "38") (name "Net-(D7-PadA)") (class "Default")
      (node (ref "D7") (pin "A") (pinfunction "A_A") (pintype "passive"))
      (node (ref "SW6") (pin "2") (pinfunction "2_2") (pintype "passive"))
    )
    (net (code "39") (name "Net-(D8-PadA)") (class "Default")
      (node (ref "D8") (pin "A") (pinfunction "A_A") (pintype "passive"))
      (node (ref "SW7") (pin "2") (pinfunction "2_2") (pintype "passive"))
    )
    (net (code "40") (name "Net-(D9-PadA)") (class "Default")
      (node (ref "D9") (pin "A") (pinfunction "A_A") (pintype "passive"))
      (node (ref "SW8") (pin "2") (pinfunction "2_2") (pintype "passive"))
    )
    (net (code "41") (name "Net-(D10-PadA)") (class "Default")
      (node (ref "D10") (pin "A") (pinfunction "A_A") (pintype "passive"))
      (node (ref "SW9") (pin "2") (pinfunction "2_2") (pintype "passive"))
    )
    (net (code "42") (name "Net-(D11-PadA)") (class "Default")
      (node (ref "D11") (pin "A") (pinfunction "A_A") (pintype "passive"))
      (node (ref "SW10") (pin "2") (pinfunction "2_2") (pintype "passive"))
    )
    (net (code "43") (name "Net-(D12-PadA)") (class "Default")
      (node (ref "D12") (pin "A") (pinfunction "A_A") (pintype "passive"))
      (node (ref "SW11") (pin "2") (pinfunction "2_2") (pintype "passive"))
    )
    (net (code "44") (name "Net-(D13-PadA)") (class "Default")
      (node (ref "D13") (pin "A") (pinfunction "A_A") (pintype "passive"))
      (node (ref "SW12") (pin "2") (pinfunction "2_2") (pintype "passive"))
    )
    (net (code "45") (name "Net-(D14-PadA)") (class "Default")
      (node (ref "D14") (pin "A") (pinfunction "A_A") (pintype "passive"))
      (node (ref "SW14") (pin "2") (pinfunction "2_2") (pintype "passive"))
    )
    (net (code "46") (name "Net-(D15-PadA)") (class "Default")
      (node (ref "D15") (pin "A") (pinfunction "A_A") (pintype "passive"))
      (node (ref "SW15") (pin "2") (pinfunction "2_2") (pintype "passive"))
    )
    (net (code "47") (name "Net-(D16-PadA)") (class "Default")
      (node (ref "D16") (pin "A") (pinfunction "A_A") (pintype "passive"))
      (node (ref "SW16") (pin "2") (pinfunction "2_2") (pintype "passive"))
    )
    (net (code "48") (name "Net-(D17-PadA)") (class "Default")
      (node (ref "D17") (pin "A") (pinfunction "A_A") (pintype "passive"))
      (node (ref "SW17") (pin "2") (pinfunction "2_2") (pintype "passive"))
    )
    (net (code "49") (name "Net-(D18-PadA)") (class "Default")
      (node (ref "D18") (pin "A") (pinfunction "A_A") (pintype "passive"))
      (node (ref "SW18") (pin "2") (pinfunction "2_2") (pintype "passive"))
    )
    (net (code "50") (name "Net-(D19-PadA)") (class "Default")
      (node (ref "D19") (pin "A") (pinfunction "A_A") (pintype "passive"))
      (node (ref "SW19") (pin "2") (pinfunction "2_2") (pintype "passive"))
    )
    (net (code "51") (name "Net-(D20-PadA)") (class "Default")
      (node (ref "D20") (pin "A") (pinfunction "A_A") (pintype "passive"))
      (node (ref "SW20") (pin "2") (pinfunction "2_2") (pintype "passive"))
    )
    (net (code "52") (name "Net-(D21-PadA)") (class "Default")
      (node (ref "D21") (pin "A") (pinfunction "A_A") (pintype "passive"))
      (node (ref "SW21") (pin "2") (pinfunction "2_2") (pintype "passive"))
    )
    (net (code "53") (name "Net-(D22-PadA)") (class "Default")
      (node (ref "D22") (pin "A") (pinfunction "A_A") (pintype "passive"))
      (node (ref "SW22") (pin "2") (pinfunction "2_2") (pintype "passive"))
    )
    (net (code "54") (name "Net-(D23-PadA)") (class "Default")
      (node (ref "D23") (pin "A") (pinfunction "A_A") (pintype "passive"))
      (node (ref "SW23") (pin "2") (pinfunction "2_2") (pintype "passive"))
    )
    (net (code "55") (name "Net-(D24-PadA)") (class "Default")
      (node (ref "D24") (pin "A") (pinfunction "A_A") (pintype "passive"))
      (node (ref "SW24") (pin "2") (pinfunction "2_2") (pintype "passive"))
    )
    (net (code "56") (name "Net-(D25-PadA)") (class "Default")
      (node (ref "D25") (pin "A") (pinfunction "A_A") (pintype "passive"))
      (node (ref "SW37") (pin "2") (pinfunction "2_2") (pintype "passive"))
    )
    (net (code "57") (name "Net-(D26-PadA)") (class "Default")
      (node (ref "D26") (pin "A") (pinfunction "A_A") (pintype "passive"))
      (node (ref "SW38") (pin "2") (pinfunction "2_2") (pintype "passive"))
    )
    (net (code "58") (name "Net-(D27-PadA)") (class "Default")
      (node (ref "D27") (pin "A") (pinfunction "A_A") (pintype "passive"))
      (node (ref "SW39") (pin "2") (pinfunction "2_2") (pintype "passive"))
    )
    (net (code "59") (name "Net-(D28-PadA)") (class "Default")
      (node (ref "D28") (pin "A") (pinfunction "A_A") (pintype "passive"))
      (node (ref "SW40") (pin "2") (pinfunction "2_2") (pintype "passive"))
    )
    (net (code "60") (name "Net-(D29-PadA)") (class "Default")
      (node (ref "D29") (pin "A") (pinfunction "A_A") (pintype "passive"))
      (node (ref "SW41") (pin "2") (pinfunction "2_2") (pintype "passive"))
    )
    (net (code "61") (name "Net-(D31-PadA)") (class "Default")
      (node (ref "D31") (pin "A") (pinfunction "A_A") (pintype "passive"))
      (node (ref "SW43") (pin "2") (pinfunction "2_2") (pintype "passive"))
    )
    (net (code "62") (name "Net-(D33-PadA)") (class "Default")
      (node (ref "D33") (pin "A") (pinfunction "A_A") (pintype "passive"))
      (node (ref "SW45") (pin "2") (pinfunction "2_2") (pintype "passive"))
    )
    (net (code "63") (name "Net-(D34-PadA)") (class "Default")
      (node (ref "D34") (pin "A") (pinfunction "A_A") (pintype "passive"))
      (node (ref "SW46") (pin "2") (pinfunction "2_2") (pintype "passive"))
    )
    (net (code "64") (name "Net-(D35-PadA)") (class "Default")
      (node (ref "D35") (pin "A") (pinfunction "A_A") (pintype "passive"))
      (node (ref "SW47") (pin "2") (pinfunction "2_2") (pintype "passive"))
    )
    (net (code "65") (name "Net-(D36-PadA)") (class "Default")
      (node (ref "D36") (pin "A") (pinfunction "A_A") (pintype "passive"))
      (node (ref "SW48") (pin "2") (pinfunction "2_2") (pintype "passive"))
    )
    (net (code "66") (name "Net-(D37-PadA)") (class "Default")
      (node (ref "D37") (pin "A") (pinfunction "A_A") (pintype "passive"))
      (node (ref "SW25") (pin "2") (pinfunction "2_2") (pintype "passive"))
    )
    (net (code "67") (name "Net-(D38-PadA)") (class "Default")
      (node (ref "D38") (pin "A") (pinfunction "A_A") (pintype "passive"))
      (node (ref "SW26") (pin "2") (pinfunction "2_2") (pintype "passive"))
    )
    (net (code "68") (name "Net-(D39-PadA)") (class "Default")
      (node (ref "D39") (pin "A") (pinfunction "A_A") (pintype "passive"))
      (node (ref "SW27") (pin "2") (pinfunction "2_2") (pintype "passive"))
    )
    (net (code "69") (name "Net-(D40-PadA)") (class "Default")
      (node (ref "D40") (pin "A") (pinfunction "A_A") (pintype "passive"))
      (node (ref "SW28") (pin "2") (pinfunction "2_2") (pintype "passive"))
    )
    (net (code "70") (name "Net-(D41-PadA)") (class "Default")
      (node (ref "D41") (pin "A") (pinfunction "A_A") (pintype "passive"))
      (node (ref "SW29") (pin "2") (pinfunction "2_2") (pintype "passive"))
    )
    (net (code "71") (name "Net-(D42-PadA)") (class "Default")
      (node (ref "D42") (pin "A") (pinfunction "A_A") (pintype "passive"))
      (node (ref "SW30") (pin "2") (pinfunction "2_2") (pintype "passive"))
    )
    (net (code "72") (name "Net-(D43-PadA)") (class "Default")
      (node (ref "D43") (pin "A") (pinfunction "A_A") (pintype "passive"))
      (node (ref "SW31") (pin "2") (pinfunction "2_2") (pintype "passive"))
    )
    (net (code "73") (name "Net-(D44-PadA)") (class "Default")
      (node (ref "D44") (pin "A") (pinfunction "A_A") (pintype "passive"))
      (node (ref "SW32") (pin "2") (pinfunction "2_2") (pintype "passive"))
    )
    (net (code "74") (name "Net-(D45-PadA)") (class "Default")
      (node (ref "D45") (pin "A") (pinfunction "A_A") (pintype "passive"))
      (node (ref "SW33") (pin "2") (pinfunction "2_2") (pintype "passive"))
    )
    (net (code "75") (name "Net-(D46-PadA)") (class "Default")
      (node (ref "D46") (pin "A") (pinfunction "A_A") (pintype "passive"))
      (node (ref "SW34") (pin "2") (pinfunction "2_2") (pintype "passive"))
    )
    (net (code "76") (name "Net-(D47-PadA)") (class "Default")
      (node (ref "D47") (pin "A") (pinfunction "A_A") (pintype "passive"))
      (node (ref "SW35") (pin "2") (pinfunction "2_2") (pintype "passive"))
    )
    (net (code "77") (name "Net-(D48-PadA)") (class "Default")
      (node (ref "D48") (pin "A") (pinfunction "A_A") (pintype "passive"))
      (node (ref "SW36") (pin "2") (pinfunction "2_2") (pintype "passive"))
    )
    (net (code "78") (name "Net-(F1-Pad2)") (class "Default")
      (node (ref "F1") (pin "2") (pinfunction "2_2") (pintype "bidirectional"))
      (node (ref "J2") (pin "VBUS1") (pinfunction "VBUS_VBUS1") (pintype "bidirectional"))
      (node (ref "J2") (pin "VBUS2") (pinfunction "VBUS_VBUS2") (pintype "bidirectional"))
    )
    (net (code "79") (name "Net-(J2-CC1)") (class "Default")
      (node (ref "J2") (pin "A5") (pinfunction "CC1_A5") (pintype "bidirectional"))
      (node (ref "R16") (pin "2") (pinfunction "2_2") (pintype "passive"))
    )
    (net (code "80") (name "Net-(J2-CC2)") (class "Default")
      (node (ref "J2") (pin "B5") (pinfunction "CC2_B5") (pintype "bidirectional"))
      (node (ref "R15") (pin "2") (pinfunction "2_2") (pintype "passive"))
    )
    (net (code "81") (name "Net-(J2-D+-PadA6)") (class "Default")
      (node (ref "J2") (pin "A6") (pinfunction "D+_A6") (pintype "bidirectional"))
      (node (ref "J2") (pin "B6") (pinfunction "D+_B6") (pintype "bidirectional"))
      (node (ref "R5") (pin "2") (pinfunction "2_2") (pintype "passive"))
    )
    (net (code "82") (name "Net-(J2-D--PadA7)") (class "Default")
      (node (ref "J2") (pin "A7") (pinfunction "D-_A7") (pintype "bidirectional"))
      (node (ref "J2") (pin "B7") (pinfunction "D-_B7") (pintype "bidirectional"))
      (node (ref "R4") (pin "2") (pinfunction "2_2") (pintype "passive"))
    )
    (net (code "83") (name "Net-(U1-AREF)") (class "Default")
      (node (ref "C3") (pin "1") (pinfunction "1_1") (pintype "passive"))
      (node (ref "U1") (pin "42") (pinfunction "AREF_42") (pintype "bidirectional"))
    )
    (net (code "84") (name "Net-(U1-UCAP)") (class "Default")
      (node (ref "C4") (pin "1") (pinfunction "1_1") (pintype "passive"))
      (node (ref "U1") (pin "6") (pinfunction "UCAP_6") (pintype "bidirectional"))
    )
    (net (code "85") (name "Net-(U1-XTAL1)") (class "Default")
      (node (ref "C1") (pin "2") (pinfunction "2_2") (pintype "passive"))
      (node (ref "U1") (pin "17") (pinfunction "XTAL1_17") (pintype "bidirectional"))
      (node (ref "Y1") (pin "3") (pinfunction "2_3") (pintype "passive"))
    )
    (net (code "86") (name "Net-(U1-XTAL2)") (class "Default")
      (node (ref "C2") (pin "2") (pinfunction "2_2") (pintype "passive"))
      (node (ref "U1") (pin "16") (pinfunction "XTAL2_16") (pintype "bidirectional"))
      (node (ref "Y1") (pin "1") (pinfunction "1_1") (pintype "passive"))
    )
    (net (code "87") (name "Net-(U1-~{RESET})") (class "Default")
      (node (ref "R1") (pin "1") (pinfunction "1_1") (pintype "passive"))
      (node (ref "U1") (pin "13") (pinfunction "~{RESET}_13") (pintype "bidirectional"))
    )
    (net (code "88") (name "Net-(U2-1_DOWN_D+)") (class "Default")
      (node (ref "R3") (pin "2") (pinfunction "2_2") (pintype "passive"))
      (node (ref "U2") (pin "P$4") (pinfunction "1_DOWN_D+_P$4") (pintype "bidirectional"))
    )
    (net (code "89") (name "Net-(U2-1_DOWN_D-)") (class "Default")
      (node (ref "R2") (pin "2") (pinfunction "2_2") (pintype "passive"))
      (node (ref "U2") (pin "P$3") (pinfunction "1_DOWN_D-_P$3") (pintype "bidirectional"))
    )
    (net (code "90") (name "Net-(U2-2_DOWN_D+)") (class "Default")
      (node (ref "R7") (pin "2") (pinfunction "2_2") (pintype "passive"))
      (node (ref "U2") (pin "P$7") (pinfunction "2_DOWN_D+_P$7") (pintype "bidirectional"))
    )
    (net (code "91") (name "Net-(U2-2_DOWN_D-)") (class "Default")
      (node (ref "R6") (pin "2") (pinfunction "2_2") (pintype "passive"))
      (node (ref "U2") (pin "P$6") (pinfunction "2_DOWN_D-_P$6") (pintype "bidirectional"))
    )
    (net (code "92") (name "Net-(U2-3_DOWN_D+)") (class "Default")
      (node (ref "R9") (pin "1") (pinfunction "1_1") (pintype "passive"))
      (node (ref "U2") (pin "P$13") (pinfunction "3_DOWN_D+_P$13") (pintype "bidirectional"))
    )
    (net (code "93") (name "Net-(U2-3_DOWN_D-)") (class "Default")
      (node (ref "R8") (pin "1") (pinfunction "1_1") (pintype "passive"))
      (node (ref "U2") (pin "P$12") (pinfunction "3_DOWN_D-_P$12") (pintype "bidirectional"))
    )
    (net (code "94") (name "Net-(U2-4_DOWN_D+)") (class "Default")
      (node (ref "R11") (pin "1") (pinfunction "1_1") (pintype "passive"))
      (node (ref "U2") (pin "P$16") (pinfunction "4_DOWN_D+_P$16") (pintype "bidirectional"))
    )
    (net (code "95") (name "Net-(U2-4_DOWN_D-)") (class "Default")
      (node (ref "R10") (pin "1") (pinfunction "1_1") (pintype "passive"))
      (node (ref "U2") (pin "P$15") (pinfunction "4_DOWN_D-_P$15") (pintype "bidirectional"))
    )
    (net (code "96") (name "Net-(U2-RESET)") (class "Default")
      (node (ref "R13") (pin "1") (pinfunction "1_1") (pintype "passive"))
      (node (ref "U2") (pin "P$17") (pinfunction "RESET_P$17") (pintype "bidirectional"))
    )
    (net (code "97") (name "Net-(U2-RREF)") (class "Default")
      (node (ref "R12") (pin "2") (pinfunction "2_2") (pintype "passive"))
      (node (ref "U2") (pin "P$8") (pinfunction "RREF_P$8") (pintype "bidirectional"))
    )
    (net (code "98") (name "Net-(U2-VCC_D)") (class "Default")
      (node (ref "U2") (pin "P$14") (pinfunction "VCC_A_P$14") (pintype "bidirectional"))
      (node (ref "U2") (pin "P$21") (pinfunction "VCC_D_P$21") (pintype "bidirectional"))
      (node (ref "U2") (pin "P$28") (pinfunction "VREG_P$28") (pintype "bidirectional"))
      (node (ref "U2") (pin "P$5") (pinfunction "VCC_A_P$5") (pintype "bidirectional"))
      (node (ref "U2") (pin "P$9") (pinfunction "VCC_A_P$9") (pintype "bidirectional"))
    )
    (net (code "99") (name "Net-(U2-XIN)") (class "Default")
      (node (ref "C5") (pin "1") (pinfunction "1_1") (pintype "passive"))
      (node (ref "U2") (pin "P$10") (pinfunction "XIN_P$10") (pintype "bidirectional"))
      (node (ref "Y2") (pin "3") (pinfunction "2_3") (pintype "passive"))
    )
    (net (code "100") (name "Net-(U2-XOUT)") (class "Default")
      (node (ref "C6") (pin "1") (pinfunction "1_1") (pintype "passive"))
      (node (ref "U2") (pin "P$11") (pinfunction "XOUT_P$11") (pintype "bidirectional"))
      (node (ref "Y2") (pin "1") (pinfunction "1_1") (pintype "passive"))
    )
    (net (code "101") (name "ROW1") (class "Default")
      (node (ref "SW1") (pin "1") (pinfunction "1_1") (pintype "passive"))
      (node (ref "SW10") (pin "1") (pinfunction "1_1") (pintype "passive"))
      (node (ref "SW11") (pin "1") (pinfunction "1_1") (pintype "passive"))
      (node (ref "SW12") (pin "1") (pinfunction "1_1") (pintype "passive"))
      (node (ref "SW2") (pin "1") (pinfunction "1_1") (pintype "passive"))
      (node (ref "SW3") (pin "1") (pinfunction "1_1") (pintype "passive"))
      (node (ref "SW4") (pin "1") (pinfunction "1_1") (pintype "passive"))
      (node (ref "SW5") (pin "1") (pinfunction "1_1") (pintype "passive"))
      (node (ref "SW6") (pin "1") (pinfunction "1_1") (pintype "passive"))
      (node (ref "SW7") (pin "1") (pinfunction "1_1") (pintype "passive"))
      (node (ref "SW8") (pin "1") (pinfunction "1_1") (pintype "passive"))
      (node (ref "SW9") (pin "1") (pinfunction "1_1") (pintype "passive"))
      (node (ref "U1") (pin "29") (pinfunction "PB5(ADC12)_29") (pintype "bidirectional"))
    )
    (net (code "102") (name "ROW2") (class "Default")
      (node (ref "SW13") (pin "1") (pinfunction "1_1") (pintype "passive"))
      (node (ref "SW14") (pin "1") (pinfunction "1_1") (pintype "passive"))
      (node (ref "SW15") (pin "1") (pinfunction "1_1") (pintype "passive"))
      (node (ref "SW16") (pin "1") (pinfunction "1_1") (pintype "passive"))
      (node (ref "SW17") (pin "1") (pinfunction "1_1") (pintype "passive"))
      (node (ref "SW18") (pin "1") (pinfunction "1_1") (pintype "passive"))
      (node (ref "SW19") (pin "1") (pinfunction "1_1") (pintype "passive"))
      (node (ref "SW20") (pin "1") (pinfunction "1_1") (pintype "passive"))
      (node (ref "SW21") (pin "1") (pinfunction "1_1") (pintype "passive"))
      (node (ref "SW22") (pin "1") (pinfunction "1_1") (pintype "passive"))
      (node (ref "SW23") (pin "1") (pinfunction "1_1") (pintype "passive"))
      (node (ref "SW24") (pin "1") (pinfunction "1_1") (pintype "passive"))
      (node (ref "U1") (pin "28") (pinfunction "PB4(ADC11)_28") (pintype "bidirectional"))
    )
    (net (code "103") (name "ROW3") (class "Default")
      (node (ref "SW37") (pin "1") (pinfunction "1_1") (pintype "passive"))
      (node (ref "SW38") (pin "1") (pinfunction "1_1") (pintype "passive"))
      (node (ref "SW39") (pin "1") (pinfunction "1_1") (pintype "passive"))
      (node (ref "SW40") (pin "1") (pinfunction "1_1") (pintype "passive"))
      (node (ref "SW41") (pin "1") (pinfunction "1_1") (pintype "passive"))
      (node (ref "SW43") (pin "1") (pinfunction "1_1") (pintype "passive"))
      (node (ref "SW45") (pin "1") (pinfunction "1_1") (pintype "passive"))
      (node (ref "SW46") (pin "1") (pinfunction "1_1") (pintype "passive"))
      (node (ref "SW47") (pin "1") (pinfunction "1_1") (pintype "passive"))
      (node (ref "SW48") (pin "1") (pinfunction "1_1") (pintype "passive"))
    )
    (net (code "104") (name "ROW4") (class "Default")
      (node (ref "SW25") (pin "1") (pinfunction "1_1") (pintype "passive"))
      (node (ref "SW26") (pin "1") (pinfunction "1_1") (pintype "passive"))
      (node (ref "SW27") (pin "1") (pinfunction "1_1") (pintype "passive"))
      (node (ref "SW28") (pin "1") (pinfunction "1_1") (pintype "passive"))
      (node (ref "SW29") (pin "1") (pinfunction "1_1") (pintype "passive"))
      (node (ref "SW30") (pin "1") (pinfunction "1_1") (pintype "passive"))
      (node (ref "SW31") (pin "1") (pinfunction "1_1") (pintype "passive"))
      (node (ref "SW32") (pin "1") (pinfunction "1_1") (pintype "passive"))
      (node (ref "SW33") (pin "1") (pinfunction "1_1") (pintype "passive"))
      (node (ref "SW34") (pin "1") (pinfunction "1_1") (pintype "passive"))
      (node (ref "SW35") (pin "1") (pinfunction "1_1") (pintype "passive"))
      (node (ref "SW36") (pin "1") (pinfunction "1_1") (pintype "passive"))
    )
    (net (code "105") (name "VCC") (class "Default")
      (node (ref "F1") (pin "1") (pinfunction "1_1") (pintype "bidirectional"))
      (node (ref "G1") (pin "1") (pinfunction "VCC_1") (pintype "bidirectional"))
      (node (ref "G2") (pin "1") (pinfunction "VCC_1") (pintype "bidirectional"))
      (node (ref "G3") (pin "1") (pinfunction "VCC_1") (pintype "bidirectional"))
      (node (ref "R1") (pin "2") (pinfunction "2_2") (pintype "passive"))
      (node (ref "R13") (pin "2") (pinfunction "2_2") (pintype "passive"))
      (node (ref "U1") (pin "14") (pinfunction "VCC_14") (pintype "bidirectional"))
      (node (ref "U1") (pin "2") (pinfunction "UVCC_2") (pintype "bidirectional"))
      (node (ref "U1") (pin "24") (pinfunction "AVCC_24") (pintype "bidirectional"))
      (node (ref "U1") (pin "34") (pinfunction "VCC_34") (pintype "bidirectional"))
      (node (ref "U1") (pin "44") (pinfunction "AVCC_44") (pintype "bidirectional"))
      (node (ref "U1") (pin "7") (pinfunction "VBUS_7") (pintype "bidirectional"))
      (node (ref "U2") (pin "P$27") (pinfunction "VCC_P$27") (pintype "bidirectional"))
    )
    (net (code "106") (name "unconnected-(U1-PF1(ADC1)-Pad40)") (class "Default")
      (node (ref "U1") (pin "40") (pinfunction "PF1(ADC1)_40") (pintype "bidirectional"))
    )
    (net (code "107") (name "unconnected-(U1-PF4(ADC4)-Pad39)") (class "Default")
      (node (ref "U1") (pin "39") (pinfunction "PF4(ADC4)_39") (pintype "bidirectional"))
    )
    (net (code "108") (name "unconnected-(U1-PF5(ADC5)-Pad38)") (class "Default")
      (node (ref "U1") (pin "38") (pinfunction "PF5(ADC5)_38") (pintype "bidirectional"))
    )
    (net (code "109") (name "unconnected-(U2-1_DOWN_OVR-PadP$25)") (class "Default")
      (node (ref "U2") (pin "P$25") (pinfunction "1_DOWN_OVR_P$25") (pintype "bidirectional"))
    )
    (net (code "110") (name "unconnected-(U2-2_DOWN_OVR-PadP$24)") (class "Default")
      (node (ref "U2") (pin "P$24") (pinfunction "2_DOWN_OVR_P$24") (pintype "bidirectional"))
    )
    (net (code "111") (name "unconnected-(U2-3_DOWN_OVR-PadP$20)") (class "Default")
      (node (ref "U2") (pin "P$20") (pinfunction "3_DOWN_OVR_P$20") (pintype "bidirectional"))
    )
    (net (code "112") (name "unconnected-(U2-4_DOWN_OVR-PadP$19)") (class "Default")
      (node (ref "U2") (pin "P$19") (pinfunction "4_DOWN_OVR_P$19") (pintype "bidirectional"))
    )
    (net (code "113") (name "unconnected-(U2-PWR{slash}I2C_SDA-PadP$26)") (class "Default")
      (node (ref "U2") (pin "P$26") (pinfunction "PWR/I2C_SDA_P$26") (pintype "bidirectional"))
    )
    (net (code "114") (name "unconnected-(U2-TEST{slash}I2C_SCL-PadP$18)") (class "Default")
      (node (ref "U2") (pin "P$18") (pinfunction "TEST/I2C_SCL_P$18") (pintype "bidirectional"))
    )
  )
)
